# ProDoc_Board1.net
KiCad netlist of a schematic drawn in EasyEDA Pro
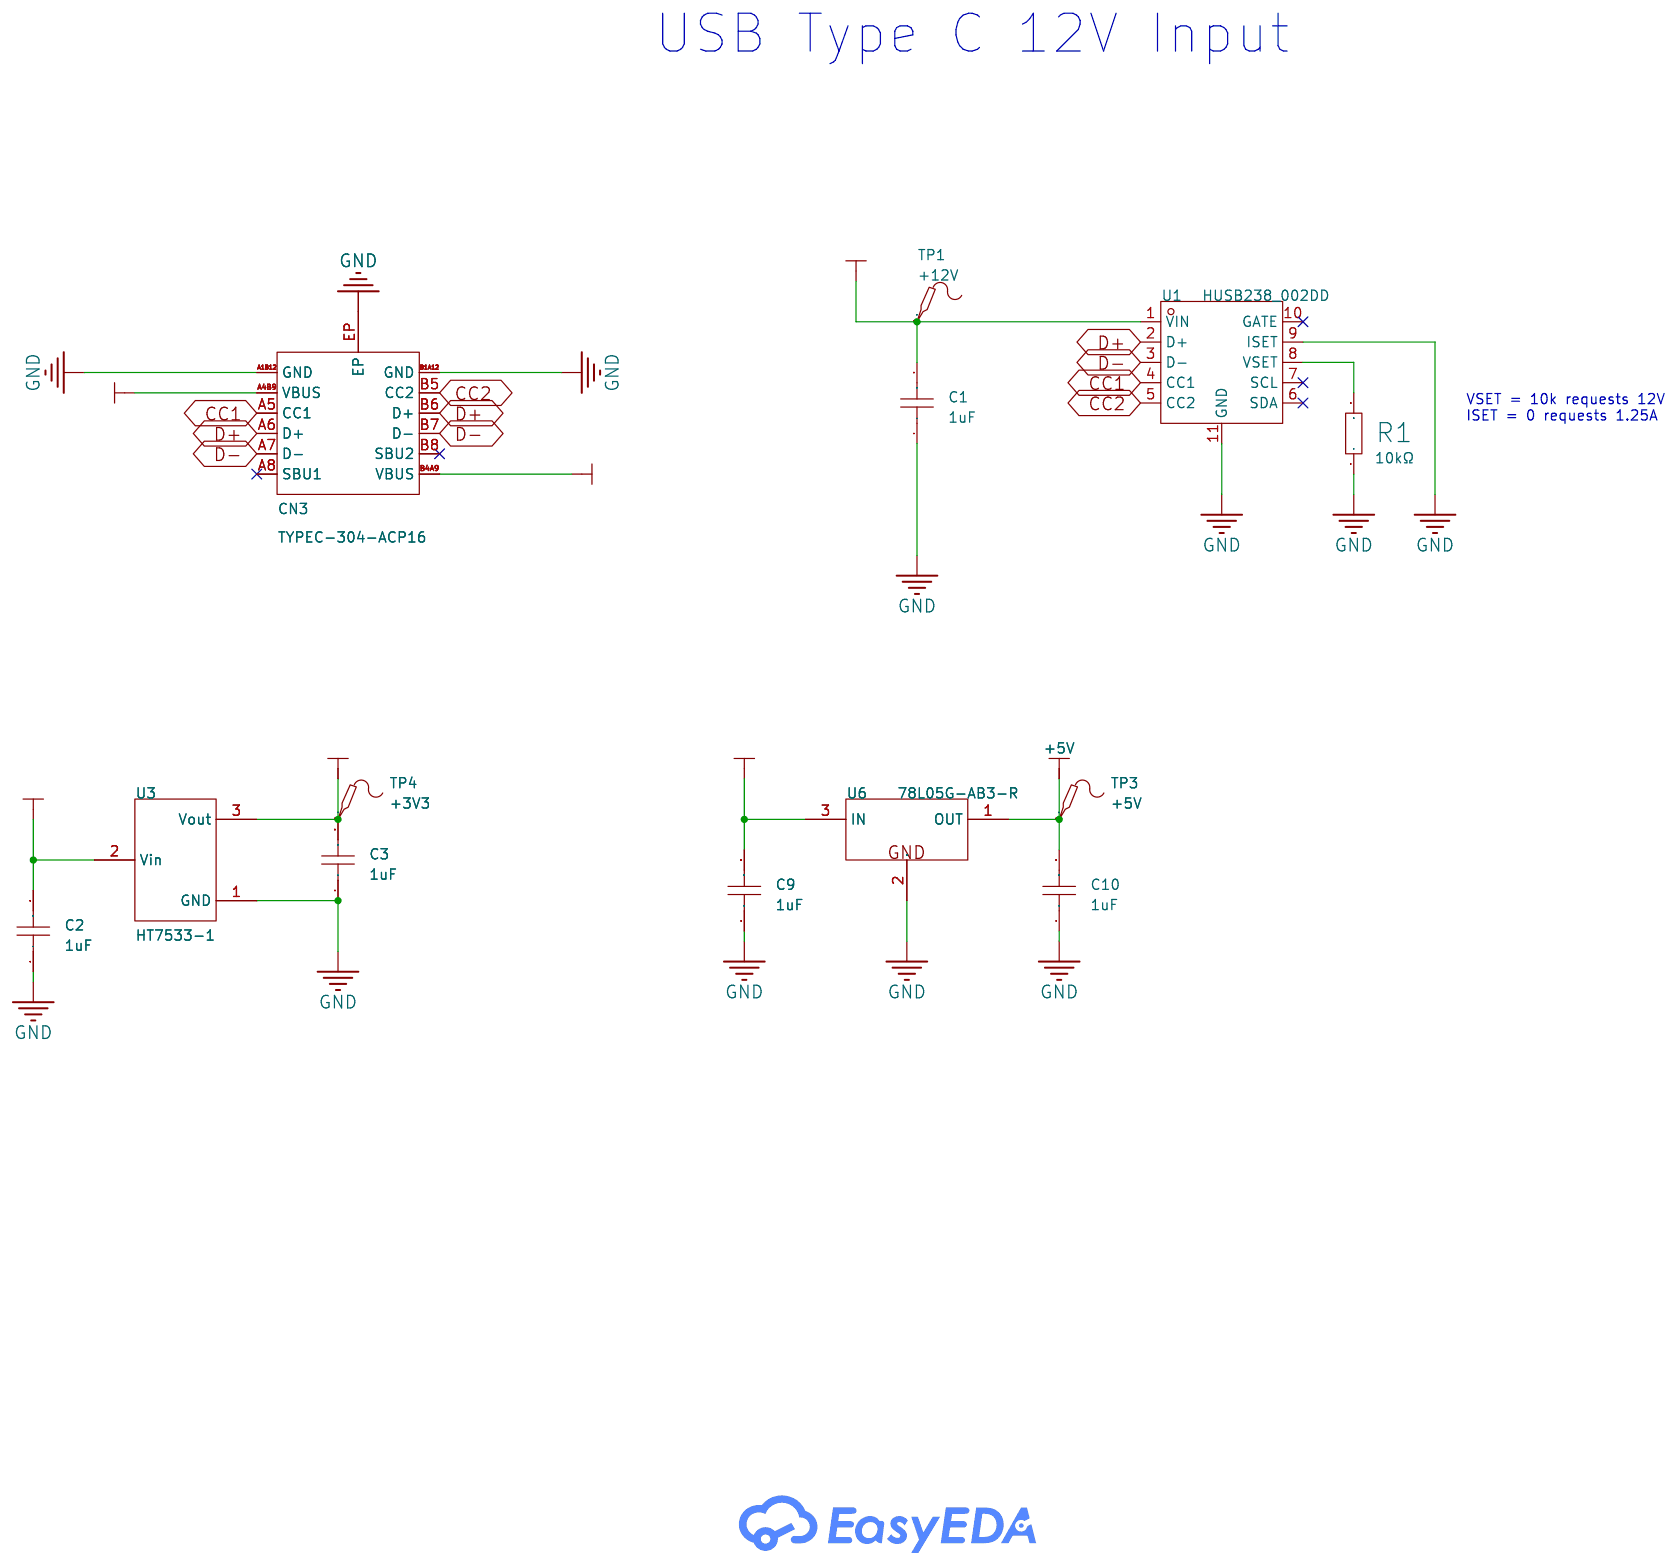
[diagram p0: P1]
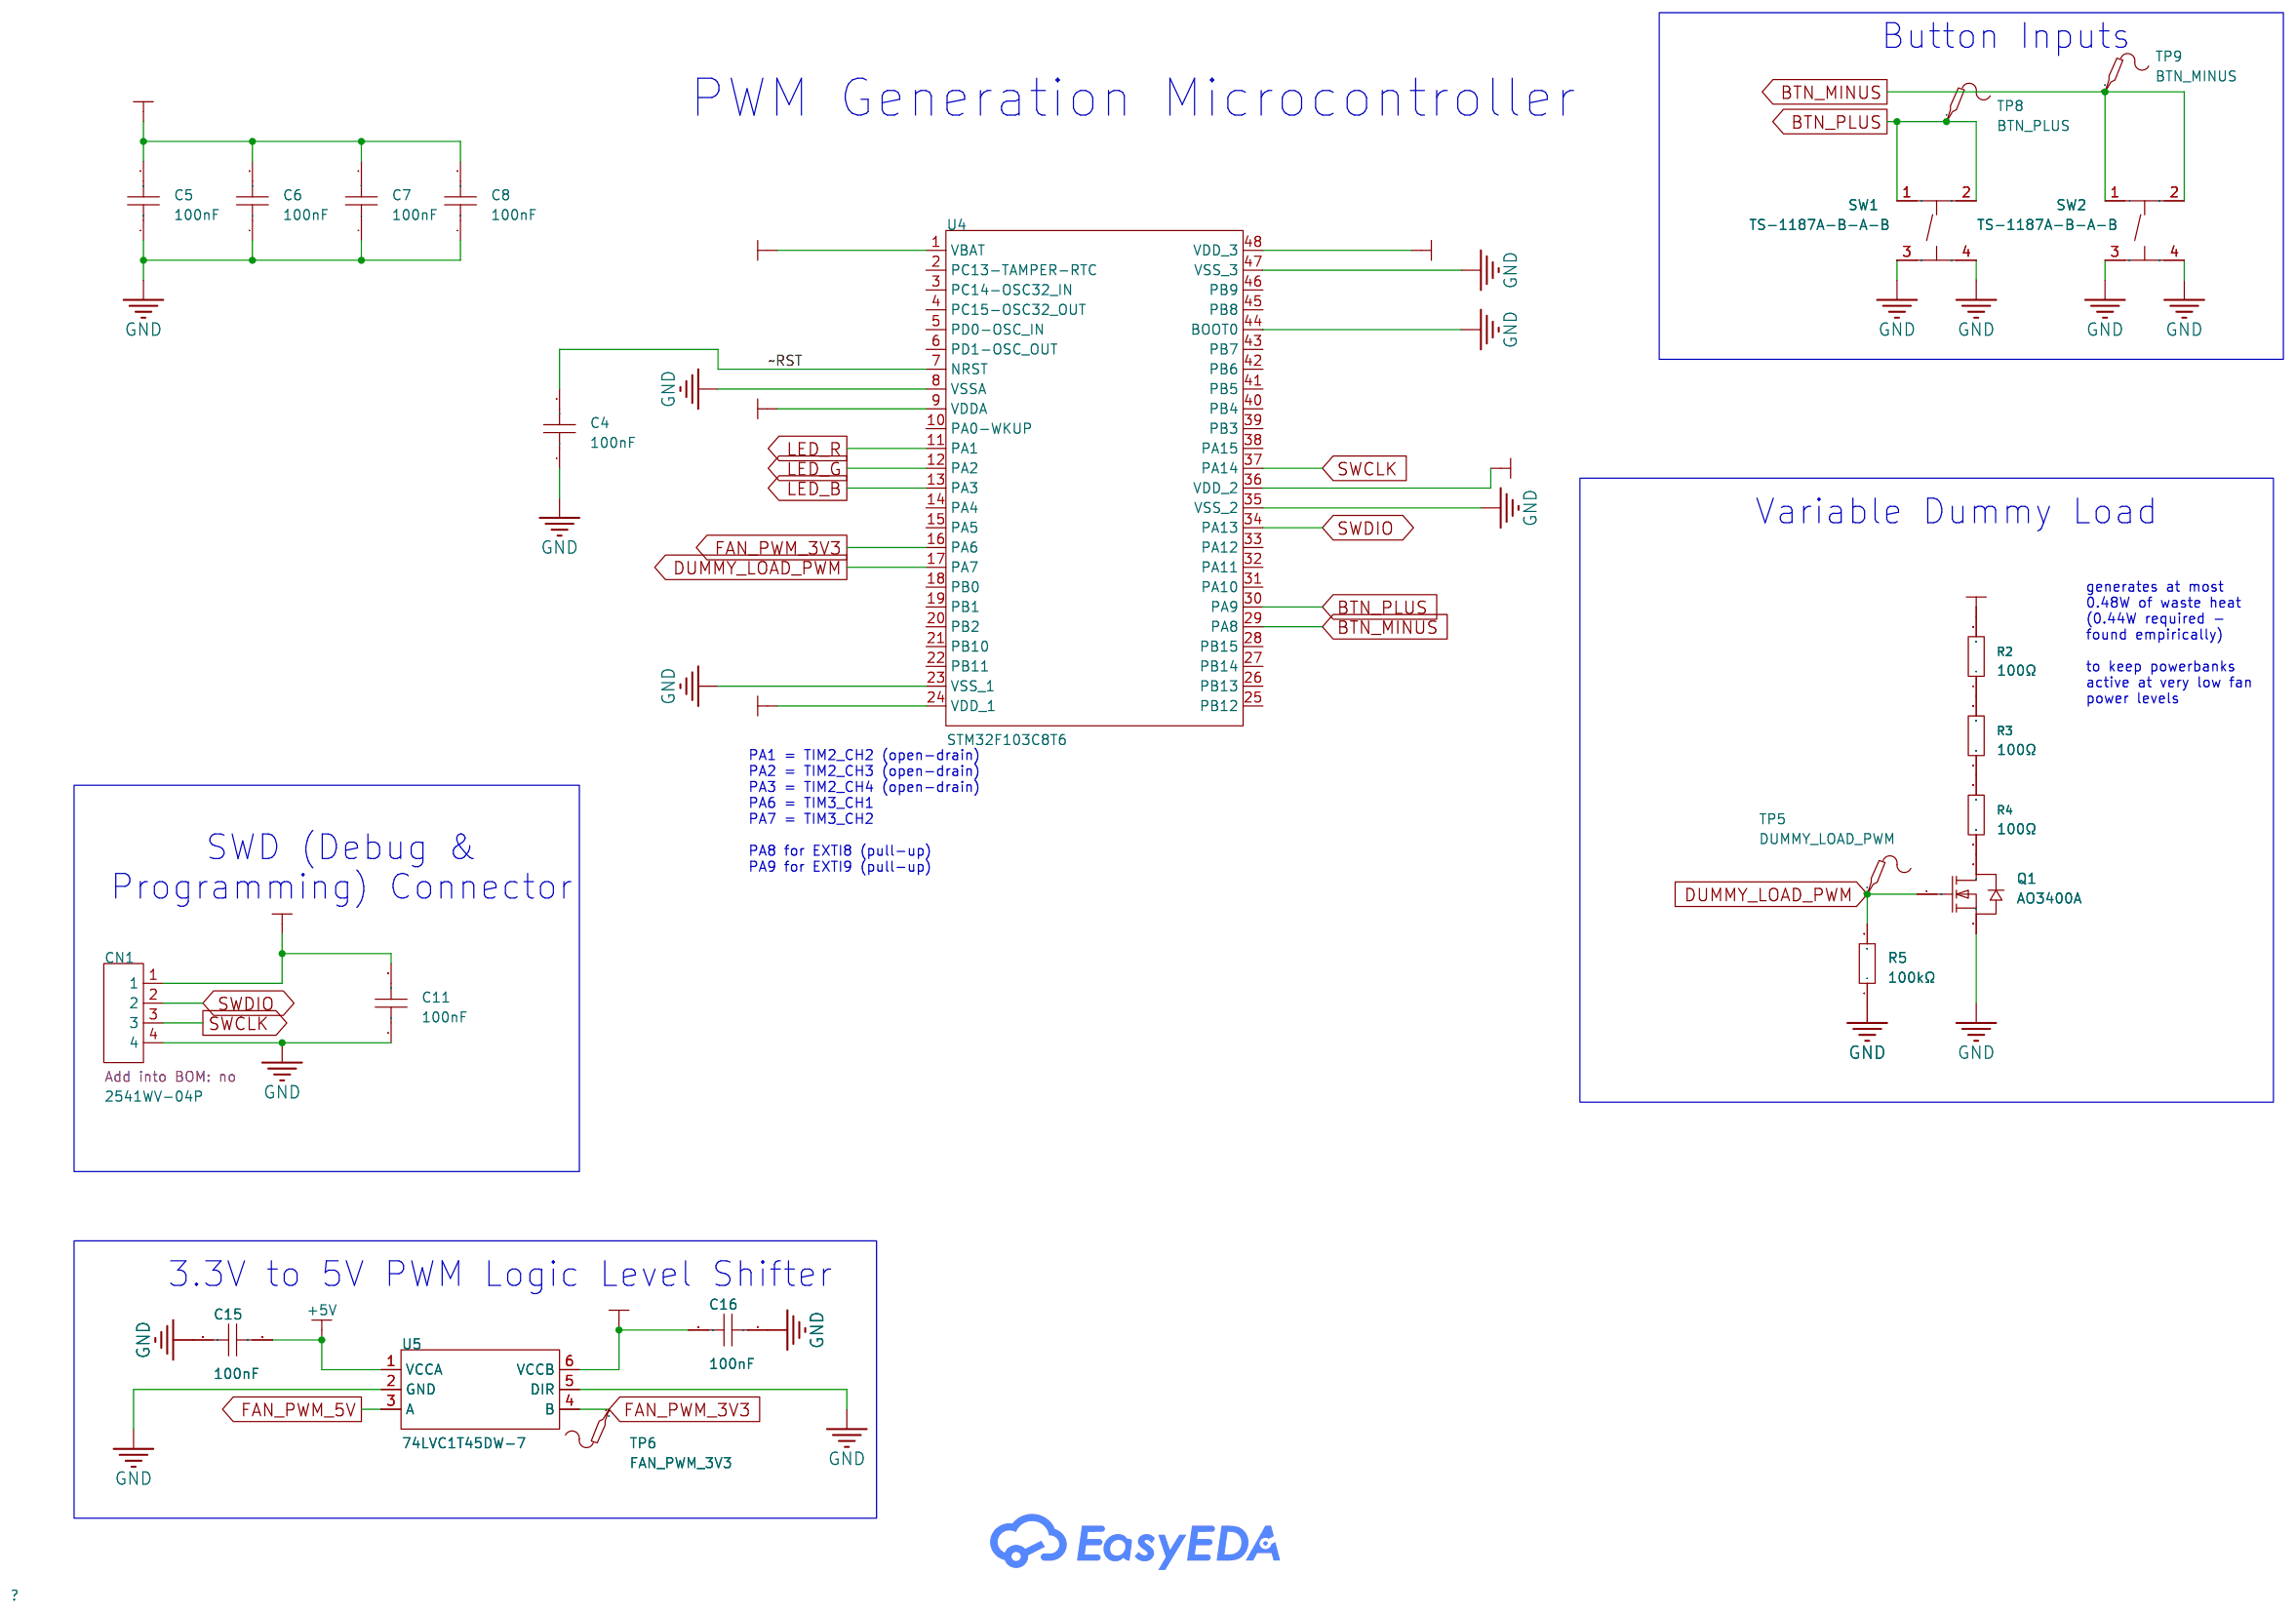
[diagram p1: P2]
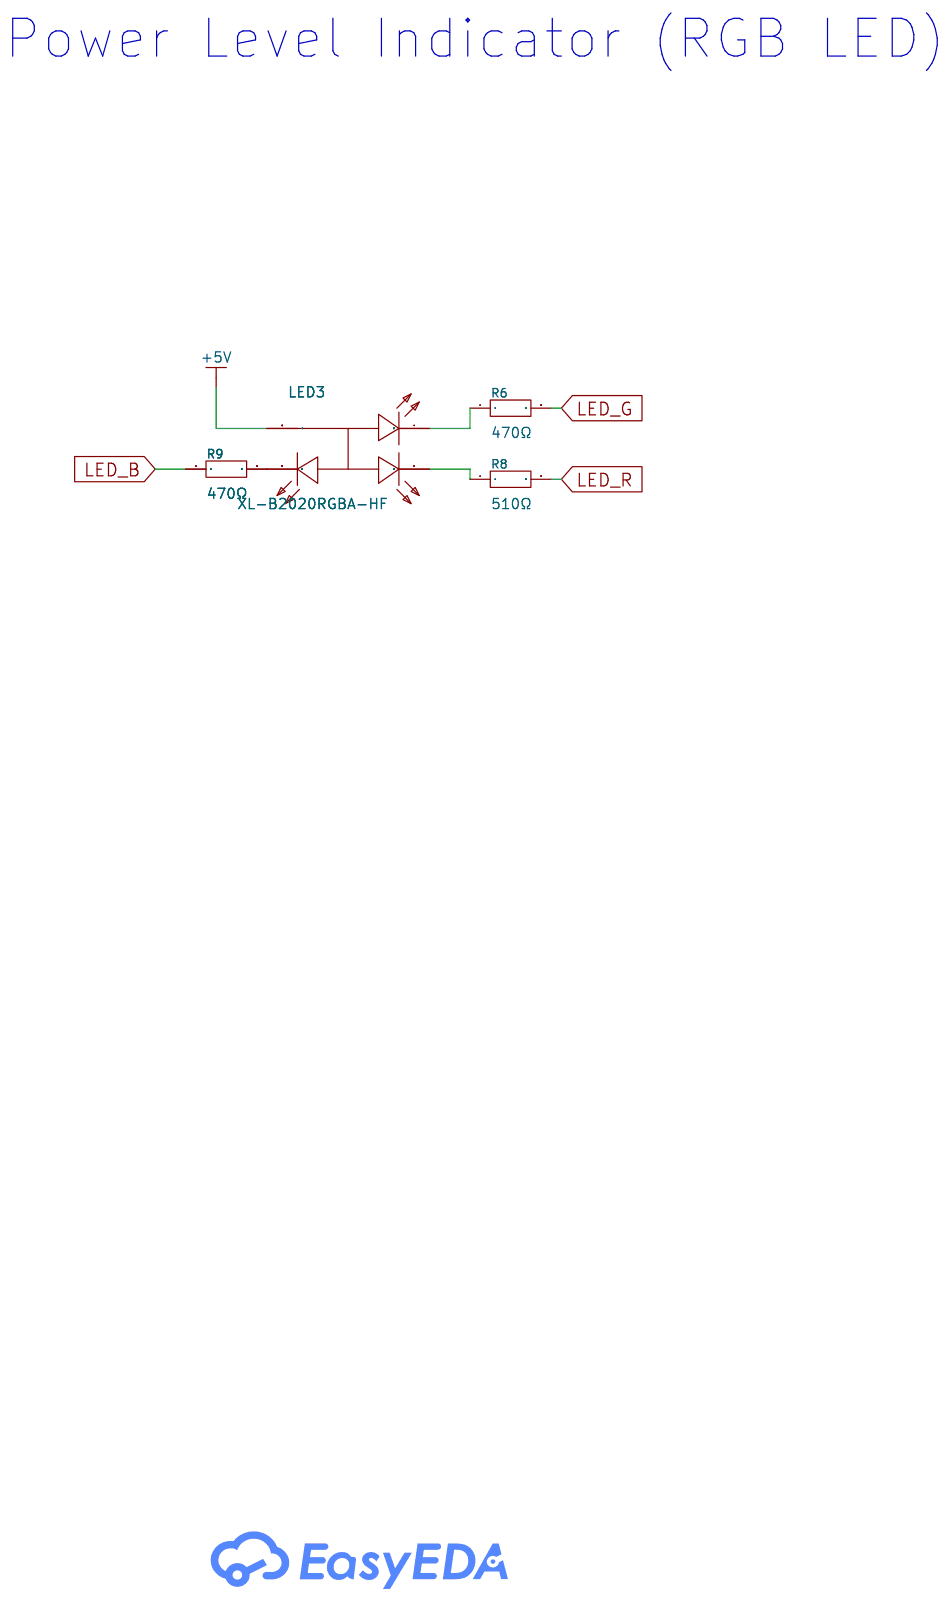
[diagram p2: P3]
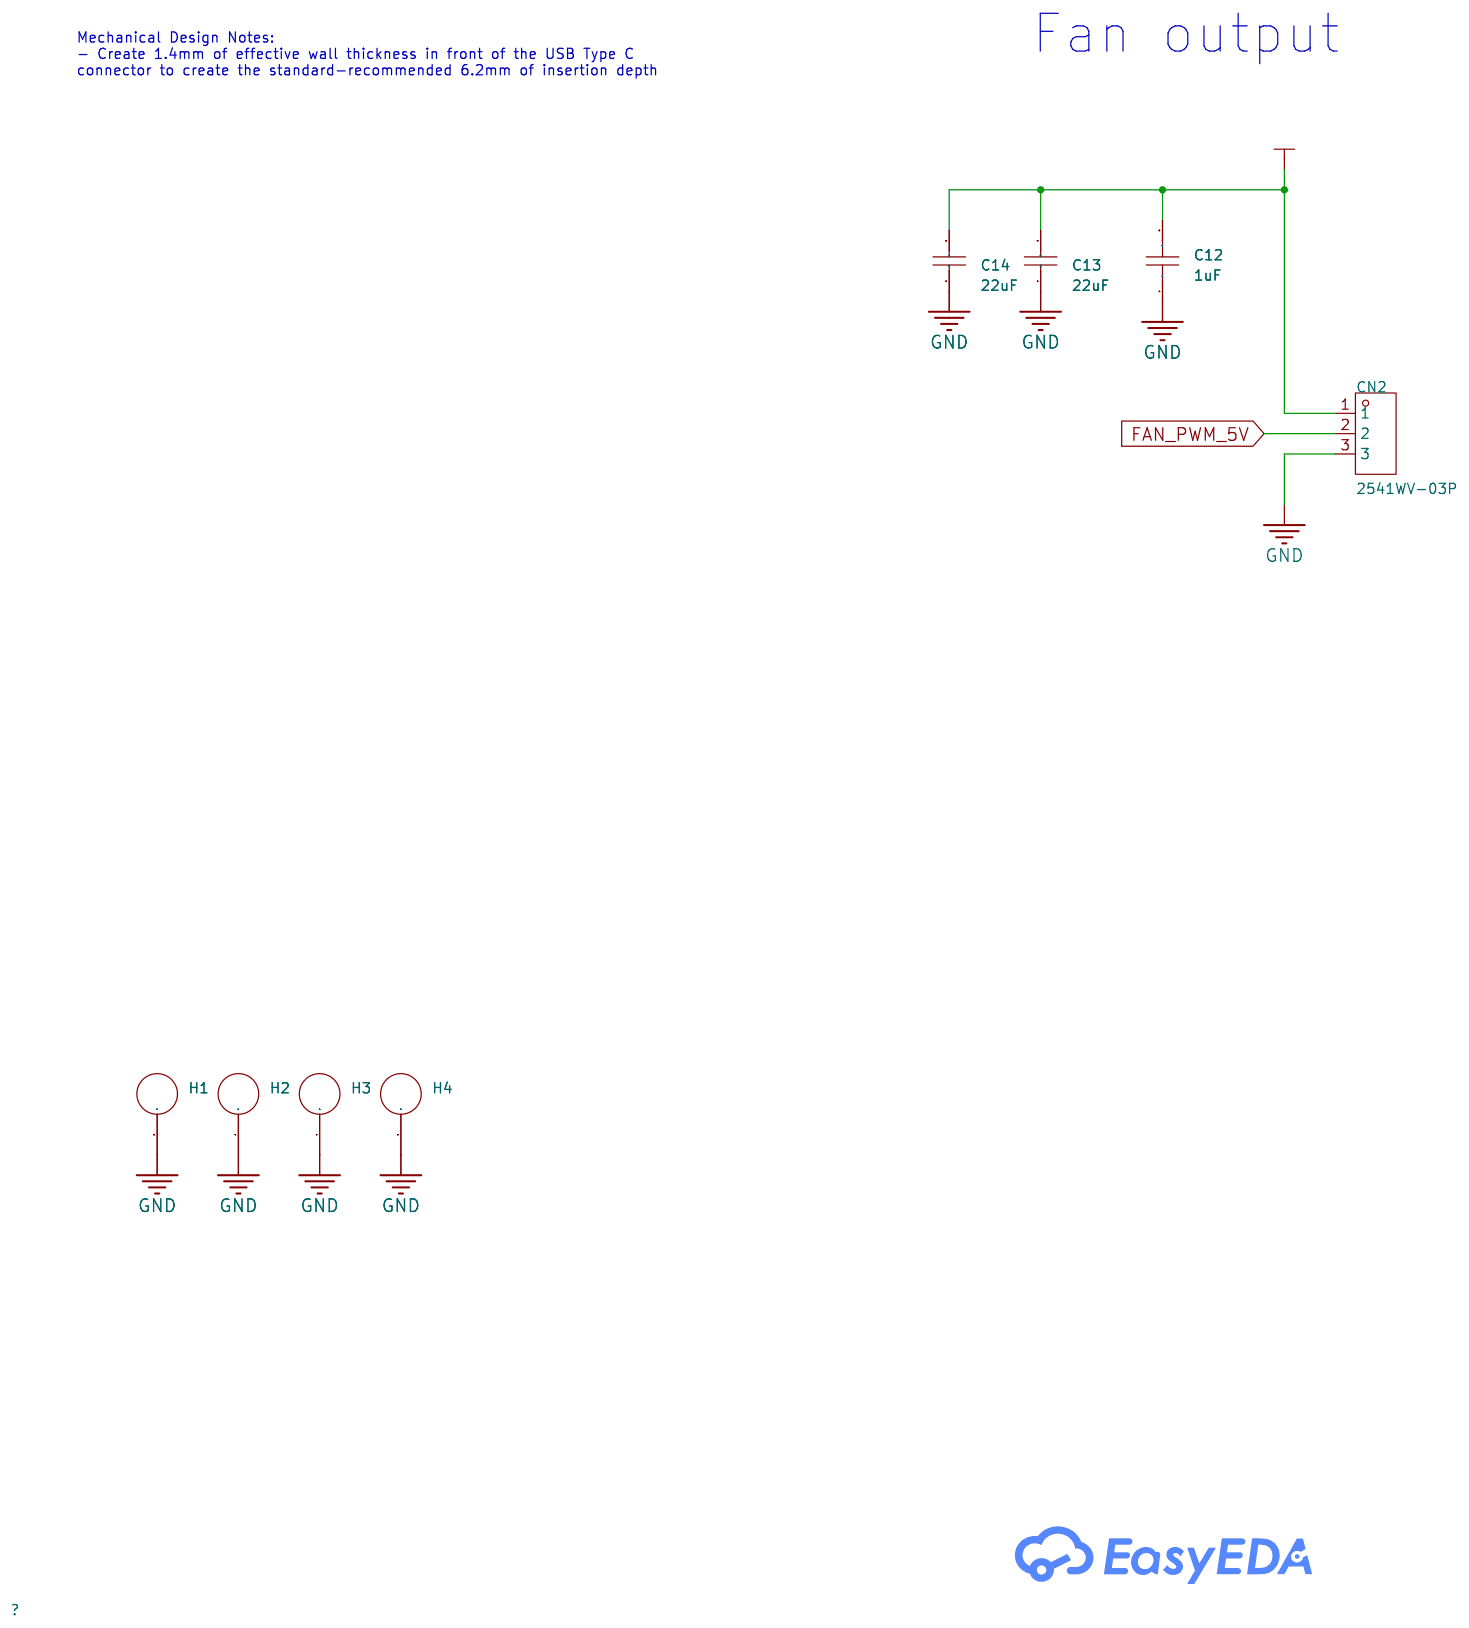
[diagram p3: P4]

(export (version "E")
  (design (tool "Eeschema 10.0.6"))
  (components
    (comp (ref "C1")
      (value "1uF")
      (footprint "easyedapro:C0603")
      (description "Capacitance:1uF Tolerance:±10% Tolerance:±10% Voltage Rating:50V Temperature Coefficient:X5R")
      (fields
        (field (name "Manufacturer Part") "CL10A105KB8NNNC")
        (field (name "Manufacturer") "SAMSUNG(三星)")
      )
      (libsource (lib "easyedapro") (part "CL10A105KB8NNNC"))
    )
    (comp (ref "C2")
      (value "1uF")
      (footprint "easyedapro:C0603")
      (description "Capacitance:1uF Tolerance:±10% Tolerance:±10% Voltage Rating:50V Temperature Coefficient:X5R")
      (fields
        (field (name "Manufacturer Part") "CL10A105KB8NNNC")
        (field (name "Manufacturer") "SAMSUNG(三星)")
      )
      (libsource (lib "easyedapro") (part "CL10A105KB8NNNC"))
    )
    (comp (ref "C3")
      (value "1uF")
      (footprint "easyedapro:C0603")
      (description "Capacitance:1uF Tolerance:±10% Tolerance:±10% Voltage Rating:50V Temperature Coefficient:X5R")
      (fields
        (field (name "Manufacturer Part") "CL10A105KB8NNNC")
        (field (name "Manufacturer") "SAMSUNG(三星)")
      )
      (libsource (lib "easyedapro") (part "CL10A105KB8NNNC"))
    )
    (comp (ref "C9")
      (value "1uF")
      (footprint "easyedapro:C0603")
      (description "Capacitance:1uF Tolerance:±10% Tolerance:±10% Voltage Rating:50V Temperature Coefficient:X5R")
      (fields
        (field (name "Manufacturer Part") "CL10A105KB8NNNC")
        (field (name "Manufacturer") "SAMSUNG(三星)")
      )
      (libsource (lib "easyedapro") (part "CL10A105KB8NNNC"))
    )
    (comp (ref "C10")
      (value "1uF")
      (footprint "easyedapro:C0603")
      (description "Capacitance:1uF Tolerance:±10% Tolerance:±10% Voltage Rating:50V Temperature Coefficient:X5R")
      (fields
        (field (name "Manufacturer Part") "CL10A105KB8NNNC")
        (field (name "Manufacturer") "SAMSUNG(三星)")
      )
      (libsource (lib "easyedapro") (part "CL10A105KB8NNNC"))
    )
    (comp (ref "CN3")
      (value "TYPEC-304-ACP16")
      (footprint "easyedapro:USB-C-SMD_TYPE-C-16P-1")
      (fields (field (name "Manufacturer") "XUNPU(讯普)"))
      (libsource (lib "easyedapro") (part "TYPEC-304-ACP16"))
    )
    (comp (ref "R1")
      (value "10kΩ")
      (footprint "easyedapro:R0603")
      (fields
        (field (name "Manufacturer Part") "0603WAF1002T5E")
        (field (name "Manufacturer") "UNI-ROYAL(厚声)")
      )
      (libsource (lib "easyedapro") (part "0603WAF1002T5E"))
    )
    (comp (ref "TP1")
      (value "+12V")
      (footprint "easyedapro:Test-Point-0.5mm")
      (description "Test Point 测试点")
      (libsource (lib "easyedapro") (part "Test-Point"))
    )
    (comp (ref "TP3")
      (value "+5V")
      (footprint "easyedapro:Test-Point-0.5mm")
      (description "Test Point 测试点")
      (libsource (lib "easyedapro") (part "Test-Point"))
    )
    (comp (ref "TP4")
      (value "+3V3")
      (footprint "easyedapro:Test-Point-0.5mm")
      (description "Test Point 测试点")
      (libsource (lib "easyedapro") (part "Test-Point"))
    )
    (comp (ref "U1")
      (value "HUSB238_002DD")
      (footprint "easyedapro:DFN-10_L3.0-W3.0-P0.50-BL-EP2.5")
      (fields (field (name "Manufacturer") "Hynetek(慧能泰)"))
      (libsource (lib "easyedapro") (part "HUSB238_002DD"))
    )
    (comp (ref "U3")
      (value "HT7533-1")
      (footprint "easyedapro:SOT-89-3_L4.5-W2.5-P1.50-LS4.2-BR")
      (fields (field (name "Manufacturer") "HOLTEK(合泰/盛群)"))
      (libsource (lib "easyedapro") (part "HT7533-1_C14289"))
    )
    (comp (ref "U6")
      (value "78L05G-AB3-R")
      (footprint "easyedapro:SOT-89-3_L4.5-W2.5-P1.50-LS4.2-BR")
      (fields (field (name "Manufacturer") "UTC(友顺)"))
      (libsource (lib "easyedapro") (part "78L05G-AB3-R"))
    )
    (comp (ref "C4")
      (value "100nF")
      (footprint "easyedapro:C0603")
      (description "Capacitance:100nF Tolerance:±10% Tolerance:±10% Voltage Rating:50V Temperature Coefficient:X7R")
      (fields
        (field (name "Manufacturer Part") "CC0603KRX7R9BB104")
        (field (name "Manufacturer") "YAGEO(国巨)")
      )
      (libsource (lib "easyedapro") (part "CC0603KRX7R9BB104"))
    )
    (comp (ref "C5")
      (value "100nF")
      (footprint "easyedapro:C0603")
      (description "Capacitance:100nF Tolerance:±10% Tolerance:±10% Voltage Rating:50V Temperature Coefficient:X7R")
      (fields
        (field (name "Manufacturer Part") "CC0603KRX7R9BB104")
        (field (name "Manufacturer") "YAGEO(国巨)")
      )
      (libsource (lib "easyedapro") (part "CC0603KRX7R9BB104"))
    )
    (comp (ref "C6")
      (value "100nF")
      (footprint "easyedapro:C0603")
      (description "Capacitance:100nF Tolerance:±10% Tolerance:±10% Voltage Rating:50V Temperature Coefficient:X7R")
      (fields
        (field (name "Manufacturer Part") "CC0603KRX7R9BB104")
        (field (name "Manufacturer") "YAGEO(国巨)")
      )
      (libsource (lib "easyedapro") (part "CC0603KRX7R9BB104"))
    )
    (comp (ref "C7")
      (value "100nF")
      (footprint "easyedapro:C0603")
      (description "Capacitance:100nF Tolerance:±10% Tolerance:±10% Voltage Rating:50V Temperature Coefficient:X7R")
      (fields
        (field (name "Manufacturer Part") "CC0603KRX7R9BB104")
        (field (name "Manufacturer") "YAGEO(国巨)")
      )
      (libsource (lib "easyedapro") (part "CC0603KRX7R9BB104"))
    )
    (comp (ref "C8")
      (value "100nF")
      (footprint "easyedapro:C0603")
      (description "Capacitance:100nF Tolerance:±10% Tolerance:±10% Voltage Rating:50V Temperature Coefficient:X7R")
      (fields
        (field (name "Manufacturer Part") "CC0603KRX7R9BB104")
        (field (name "Manufacturer") "YAGEO(国巨)")
      )
      (libsource (lib "easyedapro") (part "CC0603KRX7R9BB104"))
    )
    (comp (ref "C11")
      (value "100nF")
      (footprint "easyedapro:C0603")
      (description "Capacitance:100nF Tolerance:±10% Tolerance:±10% Voltage Rating:50V Temperature Coefficient:X7R")
      (fields
        (field (name "Manufacturer Part") "CC0603KRX7R9BB104")
        (field (name "Manufacturer") "YAGEO(国巨)")
      )
      (libsource (lib "easyedapro") (part "CC0603KRX7R9BB104"))
    )
    (comp (ref "C15")
      (value "100nF")
      (footprint "easyedapro:C0603")
      (description "Capacitance:100nF Tolerance:±10% Tolerance:±10% Voltage Rating:50V Temperature Coefficient:X7R")
      (fields
        (field (name "Manufacturer Part") "CC0603KRX7R9BB104")
        (field (name "Manufacturer") "YAGEO(国巨)")
      )
      (libsource (lib "easyedapro") (part "CC0603KRX7R9BB104"))
    )
    (comp (ref "C16")
      (value "100nF")
      (footprint "easyedapro:C0603")
      (description "Capacitance:100nF Tolerance:±10% Tolerance:±10% Voltage Rating:50V Temperature Coefficient:X7R")
      (fields
        (field (name "Manufacturer Part") "CC0603KRX7R9BB104")
        (field (name "Manufacturer") "YAGEO(国巨)")
      )
      (libsource (lib "easyedapro") (part "CC0603KRX7R9BB104"))
    )
    (comp (ref "CN1")
      (value "2541WV-04P")
      (footprint "easyedapro:HDR-TH_4P-P2.54-V-M-1")
      (fields (field (name "Manufacturer") "HanElectricity(瀚源)") (field (name "Add into BOM") "no"))
      (libsource (lib "easyedapro") (part "2541WV-04P"))
    )
    (comp (ref "Q1")
      (value "AO3400A")
      (footprint "easyedapro:SOT-23-3_L2.9-W1.3-P1.90-LS2.4-BR")
      (fields (field (name "Manufacturer") "AOS"))
      (libsource (lib "easyedapro") (part "AO3400A"))
    )
    (comp (ref "R2")
      (value "100Ω")
      (footprint "easyedapro:R1206")
      (fields
        (field (name "Manufacturer Part") "1206W4F1000T5E")
        (field (name "Manufacturer") "UNI-ROYAL(厚声)")
      )
      (libsource (lib "easyedapro") (part "1206W4F1000T5E"))
    )
    (comp (ref "R3")
      (value "100Ω")
      (footprint "easyedapro:R1206")
      (fields
        (field (name "Manufacturer Part") "1206W4F1000T5E")
        (field (name "Manufacturer") "UNI-ROYAL(厚声)")
      )
      (libsource (lib "easyedapro") (part "1206W4F1000T5E"))
    )
    (comp (ref "R4")
      (value "100Ω")
      (footprint "easyedapro:R1206")
      (fields
        (field (name "Manufacturer Part") "1206W4F1000T5E")
        (field (name "Manufacturer") "UNI-ROYAL(厚声)")
      )
      (libsource (lib "easyedapro") (part "1206W4F1000T5E"))
    )
    (comp (ref "R5")
      (value "100kΩ")
      (footprint "easyedapro:R0603")
      (fields
        (field (name "Manufacturer Part") "0603WAF1003T5E")
        (field (name "Manufacturer") "UNI-ROYAL(厚声)")
      )
      (libsource (lib "easyedapro") (part "0603WAF1003T5E"))
    )
    (comp (ref "SW1")
      (value "TS-1187A-B-A-B")
      (footprint "easyedapro:SW-SMD_4P-L5.1-W5.1-P3.70-LS6.5-TL_H1.5")
      (fields (field (name "Manufacturer") "XKB Connection(中国星坤)"))
      (libsource (lib "easyedapro") (part "TS-1187A-B-A-B"))
    )
    (comp (ref "SW2")
      (value "TS-1187A-B-A-B")
      (footprint "easyedapro:SW-SMD_4P-L5.1-W5.1-P3.70-LS6.5-TL_H1.5")
      (fields (field (name "Manufacturer") "XKB Connection(中国星坤)"))
      (libsource (lib "easyedapro") (part "TS-1187A-B-A-B"))
    )
    (comp (ref "TP5")
      (value "DUMMY_LOAD_PWM")
      (footprint "easyedapro:Test-Point-0.5mm")
      (description "Test Point 测试点")
      (libsource (lib "easyedapro") (part "Test-Point"))
    )
    (comp (ref "TP6")
      (value "FAN_PWM_3V3")
      (footprint "easyedapro:Test-Point-0.5mm")
      (description "Test Point 测试点")
      (libsource (lib "easyedapro") (part "Test-Point"))
    )
    (comp (ref "TP8")
      (value "BTN_PLUS")
      (footprint "easyedapro:Test-Point-0.5mm")
      (description "Test Point 测试点")
      (libsource (lib "easyedapro") (part "Test-Point"))
    )
    (comp (ref "TP9")
      (value "BTN_MINUS")
      (footprint "easyedapro:Test-Point-0.5mm")
      (description "Test Point 测试点")
      (libsource (lib "easyedapro") (part "Test-Point"))
    )
    (comp (ref "U4")
      (value "STM32F103C8T6")
      (footprint "easyedapro:LQFP-48_L7.0-W7.0-P0.50-LS9.0-BL")
      (fields (field (name "Manufacturer") "ST(意法半导体)"))
      (libsource (lib "easyedapro") (part "STM32F103C8T6"))
    )
    (comp (ref "U5")
      (value "74LVC1T45DW-7")
      (footprint "easyedapro:SC-70-6_L2.2-W1.3-P0.65-LS2.1-BR")
      (fields (field (name "Manufacturer") "DIODES(美台)"))
      (libsource (lib "easyedapro") (part "74LVC1T45DW-7"))
    )
    (comp (ref "LED3")
      (value "XL-B2020RGBA-HF")
      (footprint "easyedapro:LED-SMD_4P-L2.1-W2.1-P1.0-BL")
      (fields (field (name "Manufacturer") "XINGLIGHT(成兴光)"))
      (libsource (lib "easyedapro") (part "XL-B2020RGBA-HF"))
    )
    (comp (ref "R6")
      (value "470Ω")
      (footprint "easyedapro:R0402")
      (fields
        (field (name "Manufacturer Part") "0402WGF4700TCE")
        (field (name "Manufacturer") "UNI-ROYAL(厚声)")
      )
      (libsource (lib "easyedapro") (part "0402WGF4700TCE"))
    )
    (comp (ref "R8")
      (value "510Ω")
      (footprint "easyedapro:R0402")
      (fields
        (field (name "Manufacturer Part") "0402WGF5100TCE")
        (field (name "Manufacturer") "UNI-ROYAL(厚声)")
      )
      (libsource (lib "easyedapro") (part "0402WGF5100TCE"))
    )
    (comp (ref "R9")
      (value "470Ω")
      (footprint "easyedapro:R0402")
      (fields
        (field (name "Manufacturer Part") "0402WGF4700TCE")
        (field (name "Manufacturer") "UNI-ROYAL(厚声)")
      )
      (libsource (lib "easyedapro") (part "0402WGF4700TCE"))
    )
    (comp (ref "C12")
      (value "1uF")
      (footprint "easyedapro:C0603")
      (description "Capacitance:1uF Tolerance:±10% Tolerance:±10% Voltage Rating:50V Temperature Coefficient:X5R")
      (fields
        (field (name "Manufacturer Part") "CL10A105KB8NNNC")
        (field (name "Manufacturer") "SAMSUNG(三星)")
      )
      (libsource (lib "easyedapro") (part "CL10A105KB8NNNC"))
    )
    (comp (ref "C13")
      (value "22uF")
      (footprint "easyedapro:C1206")
      (description "Capacitance:22uF Tolerance:±10% Tolerance:±10% Voltage Rating:25V Temperature Coefficient:X5R")
      (fields
        (field (name "Manufacturer Part") "CL31A226KAHNNNE")
        (field (name "Manufacturer") "SAMSUNG(三星)")
      )
      (libsource (lib "easyedapro") (part "CL31A226KAHNNNE"))
    )
    (comp (ref "C14")
      (value "22uF")
      (footprint "easyedapro:C1206")
      (description "Capacitance:22uF Tolerance:±10% Tolerance:±10% Voltage Rating:25V Temperature Coefficient:X5R")
      (fields
        (field (name "Manufacturer Part") "CL31A226KAHNNNE")
        (field (name "Manufacturer") "SAMSUNG(三星)")
      )
      (libsource (lib "easyedapro") (part "CL31A226KAHNNNE"))
    )
    (comp (ref "CN2")
      (value "2541WV-03P")
      (footprint "easyedapro:HDR-TH_3P-P2.54-V-M-2")
      (fields (field (name "Manufacturer") "HanElectricity(瀚源)"))
      (libsource (lib "easyedapro") (part "2541WV-03P"))
    )
    (comp (ref "H1")
      (value "~")
      (footprint "easyedapro:HOLE_D2M5_D4M0_PAD_PTH")
      (libsource (lib "easyedapro") (part "HOLE_D2M5_D4M0_PAD_PTH"))
    )
    (comp (ref "H2")
      (value "~")
      (footprint "easyedapro:HOLE_D2M5_D4M0_PAD_PTH")
      (libsource (lib "easyedapro") (part "HOLE_D2M5_D4M0_PAD_PTH"))
    )
    (comp (ref "H3")
      (value "~")
      (footprint "easyedapro:HOLE_D2M5_D4M0_PAD_PTH")
      (libsource (lib "easyedapro") (part "HOLE_D2M5_D4M0_PAD_PTH"))
    )
    (comp (ref "H4")
      (value "~")
      (footprint "easyedapro:HOLE_D2M5_D4M0_PAD_PTH")
      (libsource (lib "easyedapro") (part "HOLE_D2M5_D4M0_PAD_PTH"))
    )
  )
  (nets
    (net (code "1") (name "+3V3") (class "Default")
      (node (ref "C11") (pin "2") (pinfunction "2_2") (pintype "unspecified"))
      (node (ref "C16") (pin "2") (pinfunction "2_2") (pintype "unspecified"))
      (node (ref "C3") (pin "2") (pinfunction "2_2") (pintype "unspecified"))
      (node (ref "C5") (pin "2") (pinfunction "2_2") (pintype "unspecified"))
      (node (ref "C6") (pin "2") (pinfunction "2_2") (pintype "unspecified"))
      (node (ref "C7") (pin "2") (pinfunction "2_2") (pintype "unspecified"))
      (node (ref "C8") (pin "2") (pinfunction "2_2") (pintype "unspecified"))
      (node (ref "CN1") (pin "1") (pinfunction "1_1") (pintype "unspecified"))
      (node (ref "TP4") (pin "1") (pinfunction "1_1") (pintype "unspecified"))
      (node (ref "U3") (pin "3") (pinfunction "Vout_3") (pintype "unspecified"))
      (node (ref "U4") (pin "1") (pinfunction "VBAT_1") (pintype "unspecified"))
      (node (ref "U4") (pin "24") (pinfunction "VDD_1_24") (pintype "unspecified"))
      (node (ref "U4") (pin "36") (pinfunction "VDD_2_36") (pintype "unspecified"))
      (node (ref "U4") (pin "48") (pinfunction "VDD_3_48") (pintype "unspecified"))
      (node (ref "U4") (pin "9") (pinfunction "VDDA_9") (pintype "unspecified"))
      (node (ref "U5") (pin "6") (pinfunction "VCCB_6") (pintype "unspecified"))
    )
    (net (code "2") (name "+5V") (class "Default")
      (node (ref "C10") (pin "2") (pinfunction "2_2") (pintype "unspecified"))
      (node (ref "C15") (pin "1") (pinfunction "1_1") (pintype "unspecified"))
      (node (ref "LED3") (pin "3") (pinfunction "A_3") (pintype "unspecified"))
      (node (ref "TP3") (pin "1") (pinfunction "1_1") (pintype "unspecified"))
      (node (ref "U5") (pin "1") (pinfunction "VCCA_1") (pintype "unspecified"))
      (node (ref "U6") (pin "1") (pinfunction "OUT_1") (pintype "unspecified"))
    )
    (net (code "3") (name "+12V") (class "Default")
      (node (ref "C1") (pin "2") (pinfunction "2_2") (pintype "unspecified"))
      (node (ref "C12") (pin "2") (pinfunction "2_2") (pintype "unspecified"))
      (node (ref "C13") (pin "2") (pinfunction "2_2") (pintype "input"))
      (node (ref "C14") (pin "2") (pinfunction "2_2") (pintype "input"))
      (node (ref "C2") (pin "2") (pinfunction "2_2") (pintype "unspecified"))
      (node (ref "C9") (pin "2") (pinfunction "2_2") (pintype "unspecified"))
      (node (ref "CN2") (pin "1") (pinfunction "1_1") (pintype "unspecified"))
      (node (ref "CN3") (pin "A4B9") (pinfunction "VBUS_A4B9") (pintype "unspecified"))
      (node (ref "CN3") (pin "B4A9") (pinfunction "VBUS_B4A9") (pintype "unspecified"))
      (node (ref "R2") (pin "2") (pinfunction "2_2") (pintype "input"))
      (node (ref "TP1") (pin "1") (pinfunction "1_1") (pintype "unspecified"))
      (node (ref "U1") (pin "1") (pinfunction "VIN_1") (pintype "unspecified"))
      (node (ref "U3") (pin "2") (pinfunction "Vin_2") (pintype "unspecified"))
      (node (ref "U6") (pin "3") (pinfunction "IN_3") (pintype "unspecified"))
    )
    (net (code "4") (name "BTN_MINUS") (class "Default")
      (node (ref "SW2") (pin "1") (pinfunction "A_1") (pintype "unspecified"))
      (node (ref "SW2") (pin "2") (pinfunction "B_2") (pintype "unspecified"))
      (node (ref "TP9") (pin "1") (pinfunction "1_1") (pintype "unspecified"))
      (node (ref "U4") (pin "29") (pinfunction "PA8_29") (pintype "unspecified"))
    )
    (net (code "5") (name "BTN_PLUS") (class "Default")
      (node (ref "SW1") (pin "1") (pinfunction "A_1") (pintype "unspecified"))
      (node (ref "SW1") (pin "2") (pinfunction "B_2") (pintype "unspecified"))
      (node (ref "TP8") (pin "1") (pinfunction "1_1") (pintype "unspecified"))
      (node (ref "U4") (pin "30") (pinfunction "PA9_30") (pintype "unspecified"))
    )
    (net (code "6") (name "CC1") (class "Default")
      (node (ref "CN3") (pin "A5") (pinfunction "CC1_A5") (pintype "unspecified"))
      (node (ref "U1") (pin "4") (pinfunction "CC1_4") (pintype "unspecified"))
    )
    (net (code "7") (name "CC2") (class "Default")
      (node (ref "CN3") (pin "B5") (pinfunction "CC2_B5") (pintype "unspecified"))
      (node (ref "U1") (pin "5") (pinfunction "CC2_5") (pintype "unspecified"))
    )
    (net (code "8") (name "D+") (class "Default")
      (node (ref "CN3") (pin "A6") (pinfunction "D+_A6") (pintype "unspecified"))
      (node (ref "CN3") (pin "B6") (pinfunction "D+_B6") (pintype "unspecified"))
      (node (ref "U1") (pin "2") (pinfunction "D+_2") (pintype "unspecified"))
    )
    (net (code "9") (name "D-") (class "Default")
      (node (ref "CN3") (pin "A7") (pinfunction "D-_A7") (pintype "unspecified"))
      (node (ref "CN3") (pin "B7") (pinfunction "D-_B7") (pintype "unspecified"))
      (node (ref "U1") (pin "3") (pinfunction "D-_3") (pintype "unspecified"))
    )
    (net (code "10") (name "DUMMY_LOAD_PWM") (class "Default")
      (node (ref "Q1") (pin "1") (pinfunction "G_1") (pintype "unspecified"))
      (node (ref "R5") (pin "2") (pinfunction "2_2") (pintype "input"))
      (node (ref "TP5") (pin "1") (pinfunction "1_1") (pintype "unspecified"))
      (node (ref "U4") (pin "17") (pinfunction "PA7_17") (pintype "unspecified"))
    )
    (net (code "11") (name "FAN_PWM_3V3") (class "Default")
      (node (ref "TP6") (pin "1") (pinfunction "1_1") (pintype "unspecified"))
      (node (ref "U4") (pin "16") (pinfunction "PA6_16") (pintype "unspecified"))
      (node (ref "U5") (pin "4") (pinfunction "B_4") (pintype "unspecified"))
    )
    (net (code "12") (name "FAN_PWM_5V") (class "Default")
      (node (ref "CN2") (pin "2") (pinfunction "2_2") (pintype "unspecified"))
      (node (ref "U5") (pin "3") (pinfunction "A_3") (pintype "unspecified"))
    )
    (net (code "13") (name "GND") (class "Default")
      (node (ref "C1") (pin "1") (pinfunction "1_1") (pintype "unspecified"))
      (node (ref "C10") (pin "1") (pinfunction "1_1") (pintype "unspecified"))
      (node (ref "C11") (pin "1") (pinfunction "1_1") (pintype "unspecified"))
      (node (ref "C12") (pin "1") (pinfunction "1_1") (pintype "unspecified"))
      (node (ref "C13") (pin "1") (pinfunction "1_1") (pintype "input"))
      (node (ref "C14") (pin "1") (pinfunction "1_1") (pintype "input"))
      (node (ref "C15") (pin "2") (pinfunction "2_2") (pintype "unspecified"))
      (node (ref "C16") (pin "1") (pinfunction "1_1") (pintype "unspecified"))
      (node (ref "C2") (pin "1") (pinfunction "1_1") (pintype "unspecified"))
      (node (ref "C3") (pin "1") (pinfunction "1_1") (pintype "unspecified"))
      (node (ref "C4") (pin "1") (pinfunction "1_1") (pintype "unspecified"))
      (node (ref "C5") (pin "1") (pinfunction "1_1") (pintype "unspecified"))
      (node (ref "C6") (pin "1") (pinfunction "1_1") (pintype "unspecified"))
      (node (ref "C7") (pin "1") (pinfunction "1_1") (pintype "unspecified"))
      (node (ref "C8") (pin "1") (pinfunction "1_1") (pintype "unspecified"))
      (node (ref "C9") (pin "1") (pinfunction "1_1") (pintype "unspecified"))
      (node (ref "CN1") (pin "4") (pinfunction "4_4") (pintype "unspecified"))
      (node (ref "CN2") (pin "3") (pinfunction "3_3") (pintype "unspecified"))
      (node (ref "CN3") (pin "A1B12") (pinfunction "GND_A1B12") (pintype "unspecified"))
      (node (ref "CN3") (pin "B1A12") (pinfunction "GND_B1A12") (pintype "unspecified"))
      (node (ref "CN3") (pin "EP") (pinfunction "EP_EP") (pintype "unspecified"))
      (node (ref "H1") (pin "1") (pinfunction "1_1") (pintype "input"))
      (node (ref "H2") (pin "1") (pinfunction "1_1") (pintype "input"))
      (node (ref "H3") (pin "1") (pinfunction "1_1") (pintype "input"))
      (node (ref "H4") (pin "1") (pinfunction "1_1") (pintype "input"))
      (node (ref "Q1") (pin "2") (pinfunction "S_2") (pintype "unspecified"))
      (node (ref "R1") (pin "1") (pinfunction "1_1") (pintype "input"))
      (node (ref "R5") (pin "1") (pinfunction "1_1") (pintype "input"))
      (node (ref "SW1") (pin "3") (pinfunction "C_3") (pintype "unspecified"))
      (node (ref "SW1") (pin "4") (pinfunction "D_4") (pintype "unspecified"))
      (node (ref "SW2") (pin "3") (pinfunction "C_3") (pintype "unspecified"))
      (node (ref "SW2") (pin "4") (pinfunction "D_4") (pintype "unspecified"))
      (node (ref "U1") (pin "11") (pinfunction "GND_11") (pintype "unspecified"))
      (node (ref "U1") (pin "9") (pinfunction "ISET_9") (pintype "unspecified"))
      (node (ref "U3") (pin "1") (pinfunction "GND_1") (pintype "unspecified"))
      (node (ref "U4") (pin "23") (pinfunction "VSS_1_23") (pintype "unspecified"))
      (node (ref "U4") (pin "35") (pinfunction "VSS_2_35") (pintype "unspecified"))
      (node (ref "U4") (pin "44") (pinfunction "BOOT0_44") (pintype "unspecified"))
      (node (ref "U4") (pin "47") (pinfunction "VSS_3_47") (pintype "unspecified"))
      (node (ref "U4") (pin "8") (pinfunction "VSSA_8") (pintype "unspecified"))
      (node (ref "U5") (pin "2") (pinfunction "GND_2") (pintype "unspecified"))
      (node (ref "U5") (pin "5") (pinfunction "DIR_5") (pintype "unspecified"))
      (node (ref "U6") (pin "2") (pinfunction "GND_2") (pintype "unspecified"))
    )
    (net (code "14") (name "LED_B") (class "Default")
      (node (ref "R9") (pin "1") (pinfunction "1_1") (pintype "input"))
      (node (ref "U4") (pin "13") (pinfunction "PA3_13") (pintype "unspecified"))
    )
    (net (code "15") (name "LED_G") (class "Default")
      (node (ref "R6") (pin "2") (pinfunction "2_2") (pintype "input"))
      (node (ref "U4") (pin "12") (pinfunction "PA2_12") (pintype "unspecified"))
    )
    (net (code "16") (name "LED_R") (class "Default")
      (node (ref "R8") (pin "2") (pinfunction "2_2") (pintype "input"))
      (node (ref "U4") (pin "11") (pinfunction "PA1_11") (pintype "unspecified"))
    )
    (net (code "17") (name "Net-(LED3-C-Pad1)") (class "Default")
      (node (ref "LED3") (pin "1") (pinfunction "C_1") (pintype "unspecified"))
      (node (ref "R8") (pin "1") (pinfunction "1_1") (pintype "input"))
    )
    (net (code "18") (name "Net-(LED3-C-Pad2)") (class "Default")
      (node (ref "LED3") (pin "2") (pinfunction "C_2") (pintype "unspecified"))
      (node (ref "R9") (pin "2") (pinfunction "2_2") (pintype "input"))
    )
    (net (code "19") (name "Net-(LED3-C-Pad4)") (class "Default")
      (node (ref "LED3") (pin "4") (pinfunction "C_4") (pintype "unspecified"))
      (node (ref "R6") (pin "1") (pinfunction "1_1") (pintype "input"))
    )
    (net (code "20") (name "Net-(Q1-D)") (class "Default")
      (node (ref "Q1") (pin "3") (pinfunction "D_3") (pintype "unspecified"))
      (node (ref "R4") (pin "1") (pinfunction "1_1") (pintype "input"))
    )
    (net (code "21") (name "Net-(R2-Pad1)") (class "Default")
      (node (ref "R2") (pin "1") (pinfunction "1_1") (pintype "input"))
      (node (ref "R3") (pin "2") (pinfunction "2_2") (pintype "input"))
    )
    (net (code "22") (name "Net-(R3-Pad1)") (class "Default")
      (node (ref "R3") (pin "1") (pinfunction "1_1") (pintype "input"))
      (node (ref "R4") (pin "2") (pinfunction "2_2") (pintype "input"))
    )
    (net (code "23") (name "Net-(U1-VSET)") (class "Default")
      (node (ref "R1") (pin "2") (pinfunction "2_2") (pintype "input"))
      (node (ref "U1") (pin "8") (pinfunction "VSET_8") (pintype "unspecified"))
    )
    (net (code "24") (name "SWCLK") (class "Default")
      (node (ref "CN1") (pin "3") (pinfunction "3_3") (pintype "unspecified"))
      (node (ref "U4") (pin "37") (pinfunction "PA14_37") (pintype "unspecified"))
    )
    (net (code "25") (name "SWDIO") (class "Default")
      (node (ref "CN1") (pin "2") (pinfunction "2_2") (pintype "unspecified"))
      (node (ref "U4") (pin "34") (pinfunction "PA13_34") (pintype "unspecified"))
    )
    (net (code "26") (name "unconnected-(CN3-SBU1-PadA8)") (class "Default")
      (node (ref "CN3") (pin "A8") (pinfunction "SBU1_A8") (pintype "unspecified+no_connect"))
    )
    (net (code "27") (name "unconnected-(CN3-SBU2-PadB8)") (class "Default")
      (node (ref "CN3") (pin "B8") (pinfunction "SBU2_B8") (pintype "unspecified+no_connect"))
    )
    (net (code "28") (name "unconnected-(U1-GATE-Pad10)") (class "Default")
      (node (ref "U1") (pin "10") (pinfunction "GATE_10") (pintype "unspecified+no_connect"))
    )
    (net (code "29") (name "unconnected-(U1-SCL-Pad7)") (class "Default")
      (node (ref "U1") (pin "7") (pinfunction "SCL_7") (pintype "unspecified+no_connect"))
    )
    (net (code "30") (name "unconnected-(U1-SDA-Pad6)") (class "Default")
      (node (ref "U1") (pin "6") (pinfunction "SDA_6") (pintype "unspecified+no_connect"))
    )
    (net (code "31") (name "unconnected-(U4-PA0-WKUP-Pad10)") (class "Default")
      (node (ref "U4") (pin "10") (pinfunction "PA0-WKUP_10") (pintype "unspecified"))
    )
    (net (code "32") (name "unconnected-(U4-PA4-Pad14)") (class "Default")
      (node (ref "U4") (pin "14") (pinfunction "PA4_14") (pintype "unspecified"))
    )
    (net (code "33") (name "unconnected-(U4-PA5-Pad15)") (class "Default")
      (node (ref "U4") (pin "15") (pinfunction "PA5_15") (pintype "unspecified"))
    )
    (net (code "34") (name "unconnected-(U4-PA10-Pad31)") (class "Default")
      (node (ref "U4") (pin "31") (pinfunction "PA10_31") (pintype "unspecified"))
    )
    (net (code "35") (name "unconnected-(U4-PA11-Pad32)") (class "Default")
      (node (ref "U4") (pin "32") (pinfunction "PA11_32") (pintype "unspecified"))
    )
    (net (code "36") (name "unconnected-(U4-PA12-Pad33)") (class "Default")
      (node (ref "U4") (pin "33") (pinfunction "PA12_33") (pintype "unspecified"))
    )
    (net (code "37") (name "unconnected-(U4-PA15-Pad38)") (class "Default")
      (node (ref "U4") (pin "38") (pinfunction "PA15_38") (pintype "unspecified"))
    )
    (net (code "38") (name "unconnected-(U4-PB0-Pad18)") (class "Default")
      (node (ref "U4") (pin "18") (pinfunction "PB0_18") (pintype "unspecified"))
    )
    (net (code "39") (name "unconnected-(U4-PB1-Pad19)") (class "Default")
      (node (ref "U4") (pin "19") (pinfunction "PB1_19") (pintype "unspecified"))
    )
    (net (code "40") (name "unconnected-(U4-PB2-Pad20)") (class "Default")
      (node (ref "U4") (pin "20") (pinfunction "PB2_20") (pintype "unspecified"))
    )
    (net (code "41") (name "unconnected-(U4-PB3-Pad39)") (class "Default")
      (node (ref "U4") (pin "39") (pinfunction "PB3_39") (pintype "unspecified"))
    )
    (net (code "42") (name "unconnected-(U4-PB4-Pad40)") (class "Default")
      (node (ref "U4") (pin "40") (pinfunction "PB4_40") (pintype "unspecified"))
    )
    (net (code "43") (name "unconnected-(U4-PB5-Pad41)") (class "Default")
      (node (ref "U4") (pin "41") (pinfunction "PB5_41") (pintype "unspecified"))
    )
    (net (code "44") (name "unconnected-(U4-PB6-Pad42)") (class "Default")
      (node (ref "U4") (pin "42") (pinfunction "PB6_42") (pintype "unspecified"))
    )
    (net (code "45") (name "unconnected-(U4-PB7-Pad43)") (class "Default")
      (node (ref "U4") (pin "43") (pinfunction "PB7_43") (pintype "unspecified"))
    )
    (net (code "46") (name "unconnected-(U4-PB8-Pad45)") (class "Default")
      (node (ref "U4") (pin "45") (pinfunction "PB8_45") (pintype "unspecified"))
    )
    (net (code "47") (name "unconnected-(U4-PB9-Pad46)") (class "Default")
      (node (ref "U4") (pin "46") (pinfunction "PB9_46") (pintype "unspecified"))
    )
    (net (code "48") (name "unconnected-(U4-PB10-Pad21)") (class "Default")
      (node (ref "U4") (pin "21") (pinfunction "PB10_21") (pintype "unspecified"))
    )
    (net (code "49") (name "unconnected-(U4-PB11-Pad22)") (class "Default")
      (node (ref "U4") (pin "22") (pinfunction "PB11_22") (pintype "unspecified"))
    )
    (net (code "50") (name "unconnected-(U4-PB12-Pad25)") (class "Default")
      (node (ref "U4") (pin "25") (pinfunction "PB12_25") (pintype "unspecified"))
    )
    (net (code "51") (name "unconnected-(U4-PB13-Pad26)") (class "Default")
      (node (ref "U4") (pin "26") (pinfunction "PB13_26") (pintype "unspecified"))
    )
    (net (code "52") (name "unconnected-(U4-PB14-Pad27)") (class "Default")
      (node (ref "U4") (pin "27") (pinfunction "PB14_27") (pintype "unspecified"))
    )
    (net (code "53") (name "unconnected-(U4-PB15-Pad28)") (class "Default")
      (node (ref "U4") (pin "28") (pinfunction "PB15_28") (pintype "unspecified"))
    )
    (net (code "54") (name "unconnected-(U4-PC13-TAMPER-RTC-Pad2)") (class "Default")
      (node (ref "U4") (pin "2") (pinfunction "PC13-TAMPER-RTC_2") (pintype "unspecified"))
    )
    (net (code "55") (name "unconnected-(U4-PC14-OSC32_IN-Pad3)") (class "Default")
      (node (ref "U4") (pin "3") (pinfunction "PC14-OSC32_IN_3") (pintype "unspecified"))
    )
    (net (code "56") (name "unconnected-(U4-PC15-OSC32_OUT-Pad4)") (class "Default")
      (node (ref "U4") (pin "4") (pinfunction "PC15-OSC32_OUT_4") (pintype "unspecified"))
    )
    (net (code "57") (name "unconnected-(U4-PD0-OSC_IN-Pad5)") (class "Default")
      (node (ref "U4") (pin "5") (pinfunction "PD0-OSC_IN_5") (pintype "unspecified"))
    )
    (net (code "58") (name "unconnected-(U4-PD1-OSC_OUT-Pad6)") (class "Default")
      (node (ref "U4") (pin "6") (pinfunction "PD1-OSC_OUT_6") (pintype "unspecified"))
    )
    (net (code "59") (name "~RST") (class "Default")
      (node (ref "C4") (pin "2") (pinfunction "2_2") (pintype "unspecified"))
      (node (ref "U4") (pin "7") (pinfunction "NRST_7") (pintype "unspecified"))
    )
  )
)
